# LPCB221_-_TEMPERATURE.net
KiCad netlist of a schematic drawn in Altium Designer
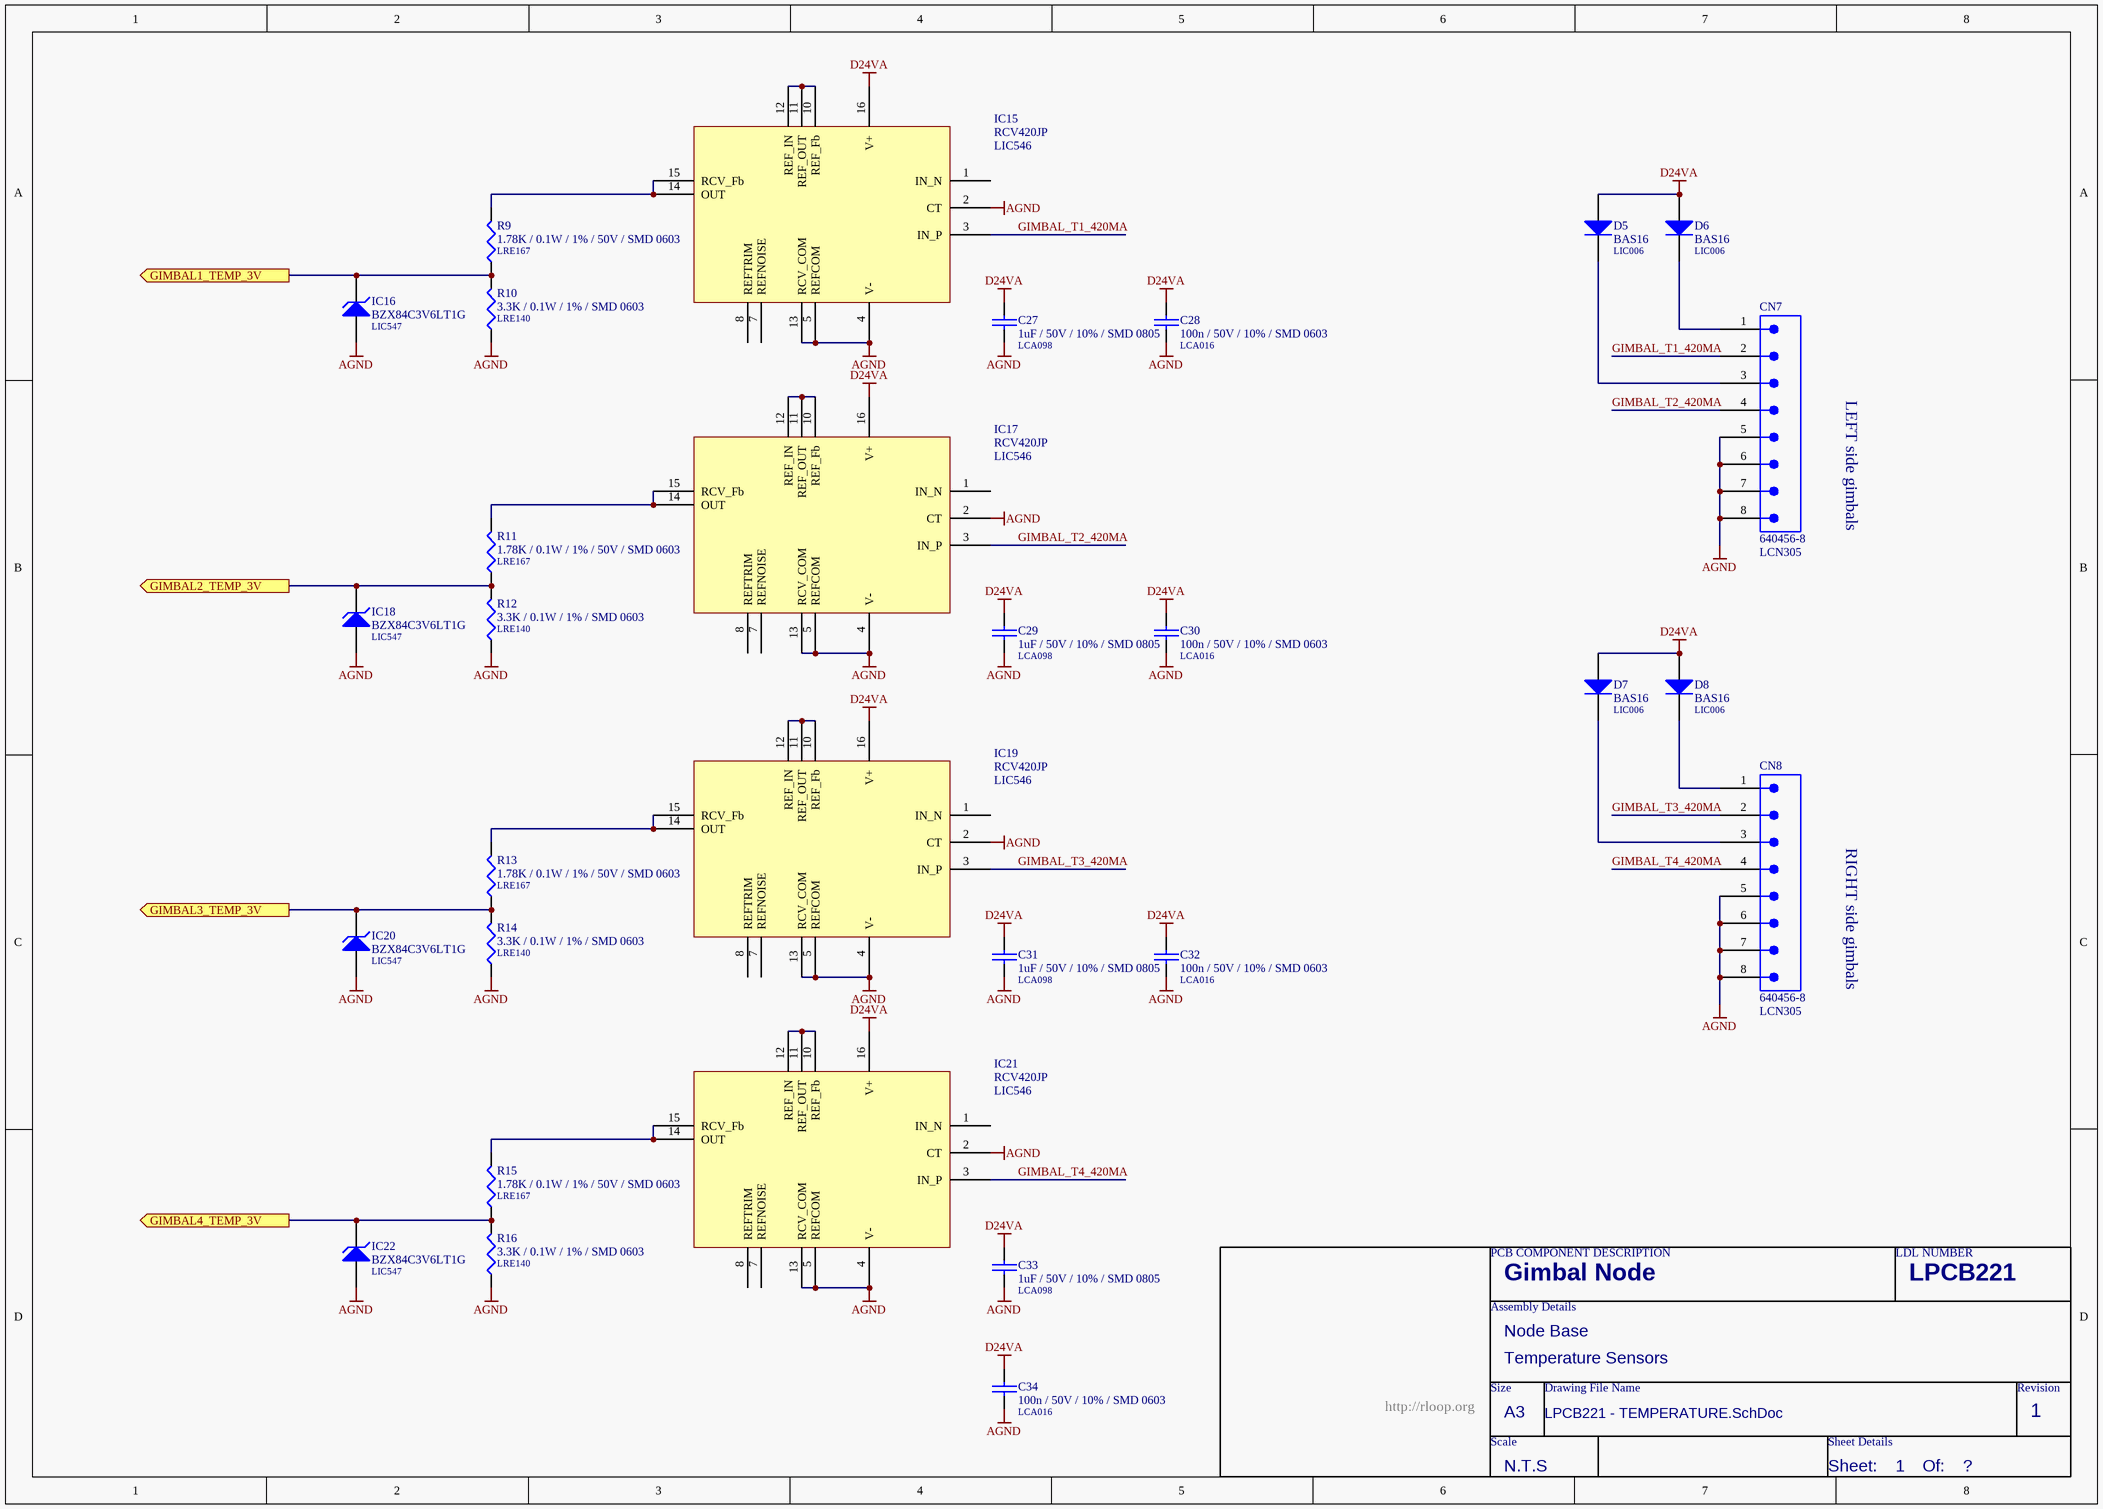
[diagram p0: LPCB221 - TEMPERATURE.SchDoc]

(export (version "E")
  (design (tool "Eeschema 10.0.6"))
  (components
    (comp (ref "C27")
      (value "1uF / 50V / 10% / SMD 0805")
      (footprint "LFP010__CC2012-0805-IPC7351_B")
      (description "Capacitor, Ceramic Chip, 1uF, 50V, SMD 0805 [LCA098]")
      (fields (field (name "LDL_NUMBER") "LCA098"))
      (libsource (lib "LDL_Capacitors") (part "1uF / 50V / 10% / SMD 0805"))
    )
    (comp (ref "C28")
      (value "100n / 50V / 10% / SMD 0603")
      (footprint "LFP011__CC1608-0603-IPC7351_B")
      (description "Capacitor, Ceramic Chip, 100nF (0.1uF), 50V, 5%, SMD 0603 [LCA016]")
      (fields (field (name "LDL_NUMBER") "LCA016"))
      (libsource (lib "LDL_Capacitors") (part "100n / 50V / 10% / SMD 0603"))
    )
    (comp (ref "C29")
      (value "1uF / 50V / 10% / SMD 0805")
      (footprint "LFP010__CC2012-0805-IPC7351_B")
      (description "Capacitor, Ceramic Chip, 1uF, 50V, SMD 0805 [LCA098]")
      (fields (field (name "LDL_NUMBER") "LCA098"))
      (libsource (lib "LDL_Capacitors") (part "1uF / 50V / 10% / SMD 0805"))
    )
    (comp (ref "C30")
      (value "100n / 50V / 10% / SMD 0603")
      (footprint "LFP011__CC1608-0603-IPC7351_B")
      (description "Capacitor, Ceramic Chip, 100nF (0.1uF), 50V, 5%, SMD 0603 [LCA016]")
      (fields (field (name "LDL_NUMBER") "LCA016"))
      (libsource (lib "LDL_Capacitors") (part "100n / 50V / 10% / SMD 0603"))
    )
    (comp (ref "C31")
      (value "1uF / 50V / 10% / SMD 0805")
      (footprint "LFP010__CC2012-0805-IPC7351_B")
      (description "Capacitor, Ceramic Chip, 1uF, 50V, SMD 0805 [LCA098]")
      (fields (field (name "LDL_NUMBER") "LCA098"))
      (libsource (lib "LDL_Capacitors") (part "1uF / 50V / 10% / SMD 0805"))
    )
    (comp (ref "C32")
      (value "100n / 50V / 10% / SMD 0603")
      (footprint "LFP011__CC1608-0603-IPC7351_B")
      (description "Capacitor, Ceramic Chip, 100nF (0.1uF), 50V, 5%, SMD 0603 [LCA016]")
      (fields (field (name "LDL_NUMBER") "LCA016"))
      (libsource (lib "LDL_Capacitors") (part "100n / 50V / 10% / SMD 0603"))
    )
    (comp (ref "C33")
      (value "1uF / 50V / 10% / SMD 0805")
      (footprint "LFP010__CC2012-0805-IPC7351_B")
      (description "Capacitor, Ceramic Chip, 1uF, 50V, SMD 0805 [LCA098]")
      (fields (field (name "LDL_NUMBER") "LCA098"))
      (libsource (lib "LDL_Capacitors") (part "1uF / 50V / 10% / SMD 0805"))
    )
    (comp (ref "C34")
      (value "100n / 50V / 10% / SMD 0603")
      (footprint "LFP011__CC1608-0603-IPC7351_B")
      (description "Capacitor, Ceramic Chip, 100nF (0.1uF), 50V, 5%, SMD 0603 [LCA016]")
      (fields (field (name "LDL_NUMBER") "LCA016"))
      (libsource (lib "LDL_Capacitors") (part "100n / 50V / 10% / SMD 0603"))
    )
    (comp (ref "CN7")
      (value "640456-8")
      (footprint "640456-8")
      (description "Connector, Male Header, 8 Way")
      (fields (field (name "LDL_NUMBER") "LCN305"))
      (libsource (lib "LDL_Connectors") (part "640456-8"))
    )
    (comp (ref "CN8")
      (value "640456-8")
      (footprint "640456-8")
      (description "Connector, Male Header, 8 Way")
      (fields (field (name "LDL_NUMBER") "LCN305"))
      (libsource (lib "LDL_Connectors") (part "640456-8"))
    )
    (comp (ref "D5")
      (value "BAS16")
      (footprint "LFP021__SOT23")
      (description "Diode, Small Signal, 0.2A, 85V, SMD SOT-23 [LIC006]")
      (fields (field (name "LDL_NUMBER") "LIC006"))
      (libsource (lib "LDL_Semiconductors") (part "BAS16"))
    )
    (comp (ref "D6")
      (value "BAS16")
      (footprint "LFP021__SOT23")
      (description "Diode, Small Signal, 0.2A, 85V, SMD SOT-23 [LIC006]")
      (fields (field (name "LDL_NUMBER") "LIC006"))
      (libsource (lib "LDL_Semiconductors") (part "BAS16"))
    )
    (comp (ref "D7")
      (value "BAS16")
      (footprint "LFP021__SOT23")
      (description "Diode, Small Signal, 0.2A, 85V, SMD SOT-23 [LIC006]")
      (fields (field (name "LDL_NUMBER") "LIC006"))
      (libsource (lib "LDL_Semiconductors") (part "BAS16"))
    )
    (comp (ref "D8")
      (value "BAS16")
      (footprint "LFP021__SOT23")
      (description "Diode, Small Signal, 0.2A, 85V, SMD SOT-23 [LIC006]")
      (fields (field (name "LDL_NUMBER") "LIC006"))
      (libsource (lib "LDL_Semiconductors") (part "BAS16"))
    )
    (comp (ref "IC15")
      (value "RCV420JP")
      (footprint "DIP-P16/X1.5")
      (description "IC, 4-20mA Interface, DIP16 [LIC546]")
      (fields (field (name "LDL_NUMBER") "LIC546"))
      (libsource (lib "LDL_Semiconductors") (part "RCV420JP"))
    )
    (comp (ref "IC16")
      (value "BZX84C3V6LT1G")
      (footprint "LFP021__SOT23")
      (description "Diode, Zener, 3.6V, 0.225W, SMD [LIC083]")
      (fields (field (name "LDL_NUMBER") "LIC547"))
      (libsource (lib "LDL_Semiconductors") (part "BZX84C3V6LT1G"))
    )
    (comp (ref "IC17")
      (value "RCV420JP")
      (footprint "DIP-P16/X1.5")
      (description "IC, 4-20mA Interface, DIP16 [LIC546]")
      (fields (field (name "LDL_NUMBER") "LIC546"))
      (libsource (lib "LDL_Semiconductors") (part "RCV420JP"))
    )
    (comp (ref "IC18")
      (value "BZX84C3V6LT1G")
      (footprint "LFP021__SOT23")
      (description "Diode, Zener, 3.6V, 0.225W, SMD [LIC083]")
      (fields (field (name "LDL_NUMBER") "LIC547"))
      (libsource (lib "LDL_Semiconductors") (part "BZX84C3V6LT1G"))
    )
    (comp (ref "IC19")
      (value "RCV420JP")
      (footprint "DIP-P16/X1.5")
      (description "IC, 4-20mA Interface, DIP16 [LIC546]")
      (fields (field (name "LDL_NUMBER") "LIC546"))
      (libsource (lib "LDL_Semiconductors") (part "RCV420JP"))
    )
    (comp (ref "IC20")
      (value "BZX84C3V6LT1G")
      (footprint "LFP021__SOT23")
      (description "Diode, Zener, 3.6V, 0.225W, SMD [LIC083]")
      (fields (field (name "LDL_NUMBER") "LIC547"))
      (libsource (lib "LDL_Semiconductors") (part "BZX84C3V6LT1G"))
    )
    (comp (ref "IC21")
      (value "RCV420JP")
      (footprint "DIP-P16/X1.5")
      (description "IC, 4-20mA Interface, DIP16 [LIC546]")
      (fields (field (name "LDL_NUMBER") "LIC546"))
      (libsource (lib "LDL_Semiconductors") (part "RCV420JP"))
    )
    (comp (ref "IC22")
      (value "BZX84C3V6LT1G")
      (footprint "LFP021__SOT23")
      (description "Diode, Zener, 3.6V, 0.225W, SMD [LIC083]")
      (fields (field (name "LDL_NUMBER") "LIC547"))
      (libsource (lib "LDL_Semiconductors") (part "BZX84C3V6LT1G"))
    )
    (comp (ref "R9")
      (value "1.78K / 0.1W / 1% / 50V / SMD 0603")
      (footprint "LFP020__CR1608-0603-IPC7351_B")
      (description "Resistor, Ceramic Chip, 1.78K, 0.1W, 1%, SMD 0603 [LRE167]")
      (fields (field (name "LDL_NUMBER") "LRE167"))
      (libsource (lib "LDL_Resistors") (part "1.78K / 0.1W / 1% / 50V / SMD 0603"))
    )
    (comp (ref "R10")
      (value "3.3K / 0.1W / 1% / SMD 0603")
      (footprint "LFP020__CR1608-0603-IPC7351_B")
      (description "Resistor, Ceramic Chip, 3.3K0, 0.1W, 1%, SMD 0603 [LRE140]")
      (fields (field (name "LDL_NUMBER") "LRE140"))
      (libsource (lib "LDL_Resistors") (part "3.3K / 0.1W / 1% / SMD 0603"))
    )
    (comp (ref "R11")
      (value "1.78K / 0.1W / 1% / 50V / SMD 0603")
      (footprint "LFP020__CR1608-0603-IPC7351_B")
      (description "Resistor, Ceramic Chip, 1.78K, 0.1W, 1%, SMD 0603 [LRE167]")
      (fields (field (name "LDL_NUMBER") "LRE167"))
      (libsource (lib "LDL_Resistors") (part "1.78K / 0.1W / 1% / 50V / SMD 0603"))
    )
    (comp (ref "R12")
      (value "3.3K / 0.1W / 1% / SMD 0603")
      (footprint "LFP020__CR1608-0603-IPC7351_B")
      (description "Resistor, Ceramic Chip, 3.3K0, 0.1W, 1%, SMD 0603 [LRE140]")
      (fields (field (name "LDL_NUMBER") "LRE140"))
      (libsource (lib "LDL_Resistors") (part "3.3K / 0.1W / 1% / SMD 0603"))
    )
    (comp (ref "R13")
      (value "1.78K / 0.1W / 1% / 50V / SMD 0603")
      (footprint "LFP020__CR1608-0603-IPC7351_B")
      (description "Resistor, Ceramic Chip, 1.78K, 0.1W, 1%, SMD 0603 [LRE167]")
      (fields (field (name "LDL_NUMBER") "LRE167"))
      (libsource (lib "LDL_Resistors") (part "1.78K / 0.1W / 1% / 50V / SMD 0603"))
    )
    (comp (ref "R14")
      (value "3.3K / 0.1W / 1% / SMD 0603")
      (footprint "LFP020__CR1608-0603-IPC7351_B")
      (description "Resistor, Ceramic Chip, 3.3K0, 0.1W, 1%, SMD 0603 [LRE140]")
      (fields (field (name "LDL_NUMBER") "LRE140"))
      (libsource (lib "LDL_Resistors") (part "3.3K / 0.1W / 1% / SMD 0603"))
    )
    (comp (ref "R15")
      (value "1.78K / 0.1W / 1% / 50V / SMD 0603")
      (footprint "LFP020__CR1608-0603-IPC7351_B")
      (description "Resistor, Ceramic Chip, 1.78K, 0.1W, 1%, SMD 0603 [LRE167]")
      (fields (field (name "LDL_NUMBER") "LRE167"))
      (libsource (lib "LDL_Resistors") (part "1.78K / 0.1W / 1% / 50V / SMD 0603"))
    )
    (comp (ref "R16")
      (value "3.3K / 0.1W / 1% / SMD 0603")
      (footprint "LFP020__CR1608-0603-IPC7351_B")
      (description "Resistor, Ceramic Chip, 3.3K0, 0.1W, 1%, SMD 0603 [LRE140]")
      (fields (field (name "LDL_NUMBER") "LRE140"))
      (libsource (lib "LDL_Resistors") (part "3.3K / 0.1W / 1% / SMD 0603"))
    )
  )
  (nets
    (net (code "1") (name "/GIMBAL1_TEMP_3V") (class "Default")
      (node (ref "IC16") (pin "3") (pinfunction "K_3") (pintype "passive"))
      (node (ref "R10") (pin "2") (pintype "passive"))
      (node (ref "R9") (pin "1") (pintype "passive"))
    )
    (net (code "2") (name "/GIMBAL2_TEMP_3V") (class "Default")
      (node (ref "IC18") (pin "3") (pinfunction "K_3") (pintype "passive"))
      (node (ref "R11") (pin "1") (pintype "passive"))
      (node (ref "R12") (pin "2") (pintype "passive"))
    )
    (net (code "3") (name "/GIMBAL3_TEMP_3V") (class "Default")
      (node (ref "IC20") (pin "3") (pinfunction "K_3") (pintype "passive"))
      (node (ref "R13") (pin "1") (pintype "passive"))
      (node (ref "R14") (pin "2") (pintype "passive"))
    )
    (net (code "4") (name "/GIMBAL4_TEMP_3V") (class "Default")
      (node (ref "IC22") (pin "3") (pinfunction "K_3") (pintype "passive"))
      (node (ref "R15") (pin "1") (pintype "passive"))
      (node (ref "R16") (pin "2") (pintype "passive"))
    )
    (net (code "5") (name "/GIMBAL_T1_420MA") (class "Default")
      (node (ref "CN7") (pin "2") (pinfunction "2_2") (pintype "passive"))
      (node (ref "IC15") (pin "3") (pinfunction "IN_P_3") (pintype "passive"))
    )
    (net (code "6") (name "/GIMBAL_T2_420MA") (class "Default")
      (node (ref "CN7") (pin "4") (pinfunction "4_4") (pintype "passive"))
      (node (ref "IC17") (pin "3") (pinfunction "IN_P_3") (pintype "passive"))
    )
    (net (code "7") (name "/GIMBAL_T3_420MA") (class "Default")
      (node (ref "CN8") (pin "2") (pinfunction "2_2") (pintype "passive"))
      (node (ref "IC19") (pin "3") (pinfunction "IN_P_3") (pintype "passive"))
    )
    (net (code "8") (name "/GIMBAL_T4_420MA") (class "Default")
      (node (ref "CN8") (pin "4") (pinfunction "4_4") (pintype "passive"))
      (node (ref "IC21") (pin "3") (pinfunction "IN_P_3") (pintype "passive"))
    )
    (net (code "9") (name "AGND") (class "Default")
      (node (ref "C27") (pin "2") (pintype "passive"))
      (node (ref "C28") (pin "2") (pintype "passive"))
      (node (ref "C29") (pin "2") (pintype "passive"))
      (node (ref "C30") (pin "2") (pintype "passive"))
      (node (ref "C31") (pin "2") (pintype "passive"))
      (node (ref "C32") (pin "2") (pintype "passive"))
      (node (ref "C33") (pin "2") (pintype "passive"))
      (node (ref "C34") (pin "2") (pintype "passive"))
      (node (ref "CN7") (pin "5") (pinfunction "5_5") (pintype "passive"))
      (node (ref "CN7") (pin "6") (pinfunction "6_6") (pintype "passive"))
      (node (ref "CN7") (pin "7") (pinfunction "7_7") (pintype "passive"))
      (node (ref "CN7") (pin "8") (pinfunction "8_8") (pintype "passive"))
      (node (ref "CN8") (pin "5") (pinfunction "5_5") (pintype "passive"))
      (node (ref "CN8") (pin "6") (pinfunction "6_6") (pintype "passive"))
      (node (ref "CN8") (pin "7") (pinfunction "7_7") (pintype "passive"))
      (node (ref "CN8") (pin "8") (pinfunction "8_8") (pintype "passive"))
      (node (ref "IC15") (pin "13") (pinfunction "RCV_COM_13") (pintype "passive"))
      (node (ref "IC15") (pin "2") (pinfunction "CT_2") (pintype "passive"))
      (node (ref "IC15") (pin "4") (pinfunction "V-_4") (pintype "power_in"))
      (node (ref "IC15") (pin "5") (pinfunction "REFCOM_5") (pintype "passive"))
      (node (ref "IC16") (pin "1") (pinfunction "A_1") (pintype "passive"))
      (node (ref "IC17") (pin "13") (pinfunction "RCV_COM_13") (pintype "passive"))
      (node (ref "IC17") (pin "2") (pinfunction "CT_2") (pintype "passive"))
      (node (ref "IC17") (pin "4") (pinfunction "V-_4") (pintype "power_in"))
      (node (ref "IC17") (pin "5") (pinfunction "REFCOM_5") (pintype "passive"))
      (node (ref "IC18") (pin "1") (pinfunction "A_1") (pintype "passive"))
      (node (ref "IC19") (pin "13") (pinfunction "RCV_COM_13") (pintype "passive"))
      (node (ref "IC19") (pin "2") (pinfunction "CT_2") (pintype "passive"))
      (node (ref "IC19") (pin "4") (pinfunction "V-_4") (pintype "power_in"))
      (node (ref "IC19") (pin "5") (pinfunction "REFCOM_5") (pintype "passive"))
      (node (ref "IC20") (pin "1") (pinfunction "A_1") (pintype "passive"))
      (node (ref "IC21") (pin "13") (pinfunction "RCV_COM_13") (pintype "passive"))
      (node (ref "IC21") (pin "2") (pinfunction "CT_2") (pintype "passive"))
      (node (ref "IC21") (pin "4") (pinfunction "V-_4") (pintype "power_in"))
      (node (ref "IC21") (pin "5") (pinfunction "REFCOM_5") (pintype "passive"))
      (node (ref "IC22") (pin "1") (pinfunction "A_1") (pintype "passive"))
      (node (ref "R10") (pin "1") (pintype "passive"))
      (node (ref "R12") (pin "1") (pintype "passive"))
      (node (ref "R14") (pin "1") (pintype "passive"))
      (node (ref "R16") (pin "1") (pintype "passive"))
    )
    (net (code "10") (name "D24VA") (class "Default")
      (node (ref "C27") (pin "1") (pintype "passive"))
      (node (ref "C28") (pin "1") (pintype "passive"))
      (node (ref "C29") (pin "1") (pintype "passive"))
      (node (ref "C30") (pin "1") (pintype "passive"))
      (node (ref "C31") (pin "1") (pintype "passive"))
      (node (ref "C32") (pin "1") (pintype "passive"))
      (node (ref "C33") (pin "1") (pintype "passive"))
      (node (ref "C34") (pin "1") (pintype "passive"))
      (node (ref "D5") (pin "1") (pinfunction "A_1") (pintype "passive"))
      (node (ref "D6") (pin "1") (pinfunction "A_1") (pintype "passive"))
      (node (ref "D7") (pin "1") (pinfunction "A_1") (pintype "passive"))
      (node (ref "D8") (pin "1") (pinfunction "A_1") (pintype "passive"))
      (node (ref "IC15") (pin "16") (pinfunction "V+_16") (pintype "power_in"))
      (node (ref "IC17") (pin "16") (pinfunction "V+_16") (pintype "power_in"))
      (node (ref "IC19") (pin "16") (pinfunction "V+_16") (pintype "power_in"))
      (node (ref "IC21") (pin "16") (pinfunction "V+_16") (pintype "power_in"))
    )
    (net (code "11") (name "Net-(D5-K)") (class "Default")
      (node (ref "CN7") (pin "3") (pinfunction "3_3") (pintype "passive"))
      (node (ref "D5") (pin "3") (pinfunction "K_3") (pintype "passive"))
    )
    (net (code "12") (name "Net-(D6-K)") (class "Default")
      (node (ref "CN7") (pin "1") (pinfunction "1_1") (pintype "passive"))
      (node (ref "D6") (pin "3") (pinfunction "K_3") (pintype "passive"))
    )
    (net (code "13") (name "Net-(D7-K)") (class "Default")
      (node (ref "CN8") (pin "3") (pinfunction "3_3") (pintype "passive"))
      (node (ref "D7") (pin "3") (pinfunction "K_3") (pintype "passive"))
    )
    (net (code "14") (name "Net-(D8-K)") (class "Default")
      (node (ref "CN8") (pin "1") (pinfunction "1_1") (pintype "passive"))
      (node (ref "D8") (pin "3") (pinfunction "K_3") (pintype "passive"))
    )
    (net (code "15") (name "Net-(IC15-OUT)") (class "Default")
      (node (ref "IC15") (pin "14") (pinfunction "OUT_14") (pintype "passive"))
      (node (ref "IC15") (pin "15") (pinfunction "RCV_Fb_15") (pintype "passive"))
      (node (ref "R9") (pin "2") (pintype "passive"))
    )
    (net (code "16") (name "Net-(IC15-REF_Fb)") (class "Default")
      (node (ref "IC15") (pin "10") (pinfunction "REF_Fb_10") (pintype "passive"))
      (node (ref "IC15") (pin "11") (pinfunction "REF_OUT_11") (pintype "passive"))
      (node (ref "IC15") (pin "12") (pinfunction "REF_IN_12") (pintype "passive"))
    )
    (net (code "17") (name "Net-(IC17-OUT)") (class "Default")
      (node (ref "IC17") (pin "14") (pinfunction "OUT_14") (pintype "passive"))
      (node (ref "IC17") (pin "15") (pinfunction "RCV_Fb_15") (pintype "passive"))
      (node (ref "R11") (pin "2") (pintype "passive"))
    )
    (net (code "18") (name "Net-(IC17-REF_Fb)") (class "Default")
      (node (ref "IC17") (pin "10") (pinfunction "REF_Fb_10") (pintype "passive"))
      (node (ref "IC17") (pin "11") (pinfunction "REF_OUT_11") (pintype "passive"))
      (node (ref "IC17") (pin "12") (pinfunction "REF_IN_12") (pintype "passive"))
    )
    (net (code "19") (name "Net-(IC19-OUT)") (class "Default")
      (node (ref "IC19") (pin "14") (pinfunction "OUT_14") (pintype "passive"))
      (node (ref "IC19") (pin "15") (pinfunction "RCV_Fb_15") (pintype "passive"))
      (node (ref "R13") (pin "2") (pintype "passive"))
    )
    (net (code "20") (name "Net-(IC19-REF_Fb)") (class "Default")
      (node (ref "IC19") (pin "10") (pinfunction "REF_Fb_10") (pintype "passive"))
      (node (ref "IC19") (pin "11") (pinfunction "REF_OUT_11") (pintype "passive"))
      (node (ref "IC19") (pin "12") (pinfunction "REF_IN_12") (pintype "passive"))
    )
    (net (code "21") (name "Net-(IC21-OUT)") (class "Default")
      (node (ref "IC21") (pin "14") (pinfunction "OUT_14") (pintype "passive"))
      (node (ref "IC21") (pin "15") (pinfunction "RCV_Fb_15") (pintype "passive"))
      (node (ref "R15") (pin "2") (pintype "passive"))
    )
    (net (code "22") (name "Net-(IC21-REF_Fb)") (class "Default")
      (node (ref "IC21") (pin "10") (pinfunction "REF_Fb_10") (pintype "passive"))
      (node (ref "IC21") (pin "11") (pinfunction "REF_OUT_11") (pintype "passive"))
      (node (ref "IC21") (pin "12") (pinfunction "REF_IN_12") (pintype "passive"))
    )
    (net (code "23") (name "unconnected-(IC15-IN_N-Pad1)") (class "Default")
      (node (ref "IC15") (pin "1") (pinfunction "IN_N_1") (pintype "passive"))
    )
    (net (code "24") (name "unconnected-(IC15-REFNOISE-Pad7)") (class "Default")
      (node (ref "IC15") (pin "7") (pinfunction "REFNOISE_7") (pintype "passive"))
    )
    (net (code "25") (name "unconnected-(IC15-REFTRIM-Pad8)") (class "Default")
      (node (ref "IC15") (pin "8") (pinfunction "REFTRIM_8") (pintype "passive"))
    )
    (net (code "26") (name "unconnected-(IC17-IN_N-Pad1)") (class "Default")
      (node (ref "IC17") (pin "1") (pinfunction "IN_N_1") (pintype "passive"))
    )
    (net (code "27") (name "unconnected-(IC17-REFNOISE-Pad7)") (class "Default")
      (node (ref "IC17") (pin "7") (pinfunction "REFNOISE_7") (pintype "passive"))
    )
    (net (code "28") (name "unconnected-(IC17-REFTRIM-Pad8)") (class "Default")
      (node (ref "IC17") (pin "8") (pinfunction "REFTRIM_8") (pintype "passive"))
    )
    (net (code "29") (name "unconnected-(IC19-IN_N-Pad1)") (class "Default")
      (node (ref "IC19") (pin "1") (pinfunction "IN_N_1") (pintype "passive"))
    )
    (net (code "30") (name "unconnected-(IC19-REFNOISE-Pad7)") (class "Default")
      (node (ref "IC19") (pin "7") (pinfunction "REFNOISE_7") (pintype "passive"))
    )
    (net (code "31") (name "unconnected-(IC19-REFTRIM-Pad8)") (class "Default")
      (node (ref "IC19") (pin "8") (pinfunction "REFTRIM_8") (pintype "passive"))
    )
    (net (code "32") (name "unconnected-(IC21-IN_N-Pad1)") (class "Default")
      (node (ref "IC21") (pin "1") (pinfunction "IN_N_1") (pintype "passive"))
    )
    (net (code "33") (name "unconnected-(IC21-REFNOISE-Pad7)") (class "Default")
      (node (ref "IC21") (pin "7") (pinfunction "REFNOISE_7") (pintype "passive"))
    )
    (net (code "34") (name "unconnected-(IC21-REFTRIM-Pad8)") (class "Default")
      (node (ref "IC21") (pin "8") (pinfunction "REFTRIM_8") (pintype "passive"))
    )
  )
)
